# MS5803-01BA_I2C.net
KiCad netlist of a schematic drawn in EAGLE
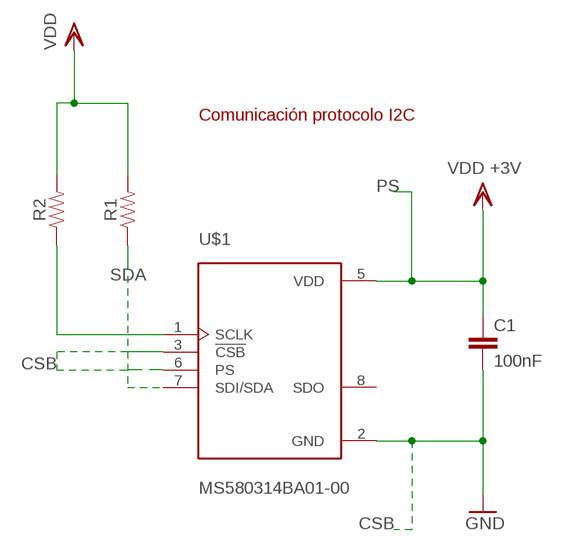
[diagram p0: schematic, sheet 1]

(export (version "E")
  (design (tool "Eeschema 10.0.6"))
  (components
    (comp (ref "C1")
      (value "100nF")
      (footprint "eagle-import:1206")
      (libsource (lib "eagle-import") (part "1.0NF/1000PF-1206-2KV-10%"))
    )
    (comp (ref "R1")
      (value "RESISTOR1206")
      (footprint "eagle-import:1206")
      (libsource (lib "eagle-import") (part "RESISTOR1206"))
    )
    (comp (ref "R2")
      (value "RESISTOR1206")
      (footprint "eagle-import:1206")
      (libsource (lib "eagle-import") (part "RESISTOR1206"))
    )
    (comp (ref "U$1")
      (value "MS580314BA01-00")
      (footprint "eagle-import:XDCR_MS580314BA01-00")
      (fields (field (name "MF") "Measurement Specialties"))
      (libsource (lib "eagle-import") (part "MS580314BA01-00"))
    )
  )
  (nets
    (net (code "1") (name "/SDA") (class "Default")
      (node (ref "R1") (pin "1") (pinfunction "1_1") (pintype "passive"))
      (node (ref "U$1") (pin "7") (pinfunction "SDI/SDA_7") (pintype "input"))
    )
    (net (code "2") (name "GND") (class "Default")
      (node (ref "C1") (pin "2") (pinfunction "2_2") (pintype "passive"))
      (node (ref "U$1") (pin "2") (pinfunction "GND_2") (pintype "passive"))
      (node (ref "U$1") (pin "3") (pinfunction "~{CSB}_3") (pintype "input"))
      (node (ref "U$1") (pin "6") (pinfunction "PS_6") (pintype "input"))
    )
    (net (code "3") (name "Net-(U$1-SCLK)") (class "Default")
      (node (ref "R2") (pin "1") (pinfunction "1_1") (pintype "passive"))
      (node (ref "U$1") (pin "1") (pinfunction "SCLK_1") (pintype "input"))
    )
    (net (code "4") (name "VDD") (class "Default")
      (node (ref "R1") (pin "2") (pinfunction "2_2") (pintype "passive"))
      (node (ref "R2") (pin "2") (pinfunction "2_2") (pintype "passive"))
    )
    (net (code "5") (name "VDD +3V") (class "Default")
      (node (ref "C1") (pin "1") (pinfunction "1_1") (pintype "passive"))
      (node (ref "U$1") (pin "5") (pinfunction "VDD_5") (pintype "power_in"))
    )
    (net (code "6") (name "unconnected-(U$1-SDO-Pad8)") (class "Default")
      (node (ref "U$1") (pin "8") (pinfunction "SDO_8") (pintype "output"))
    )
  )
)
